# controller_rev3.net
KiCad netlist of a schematic drawn in EAGLE
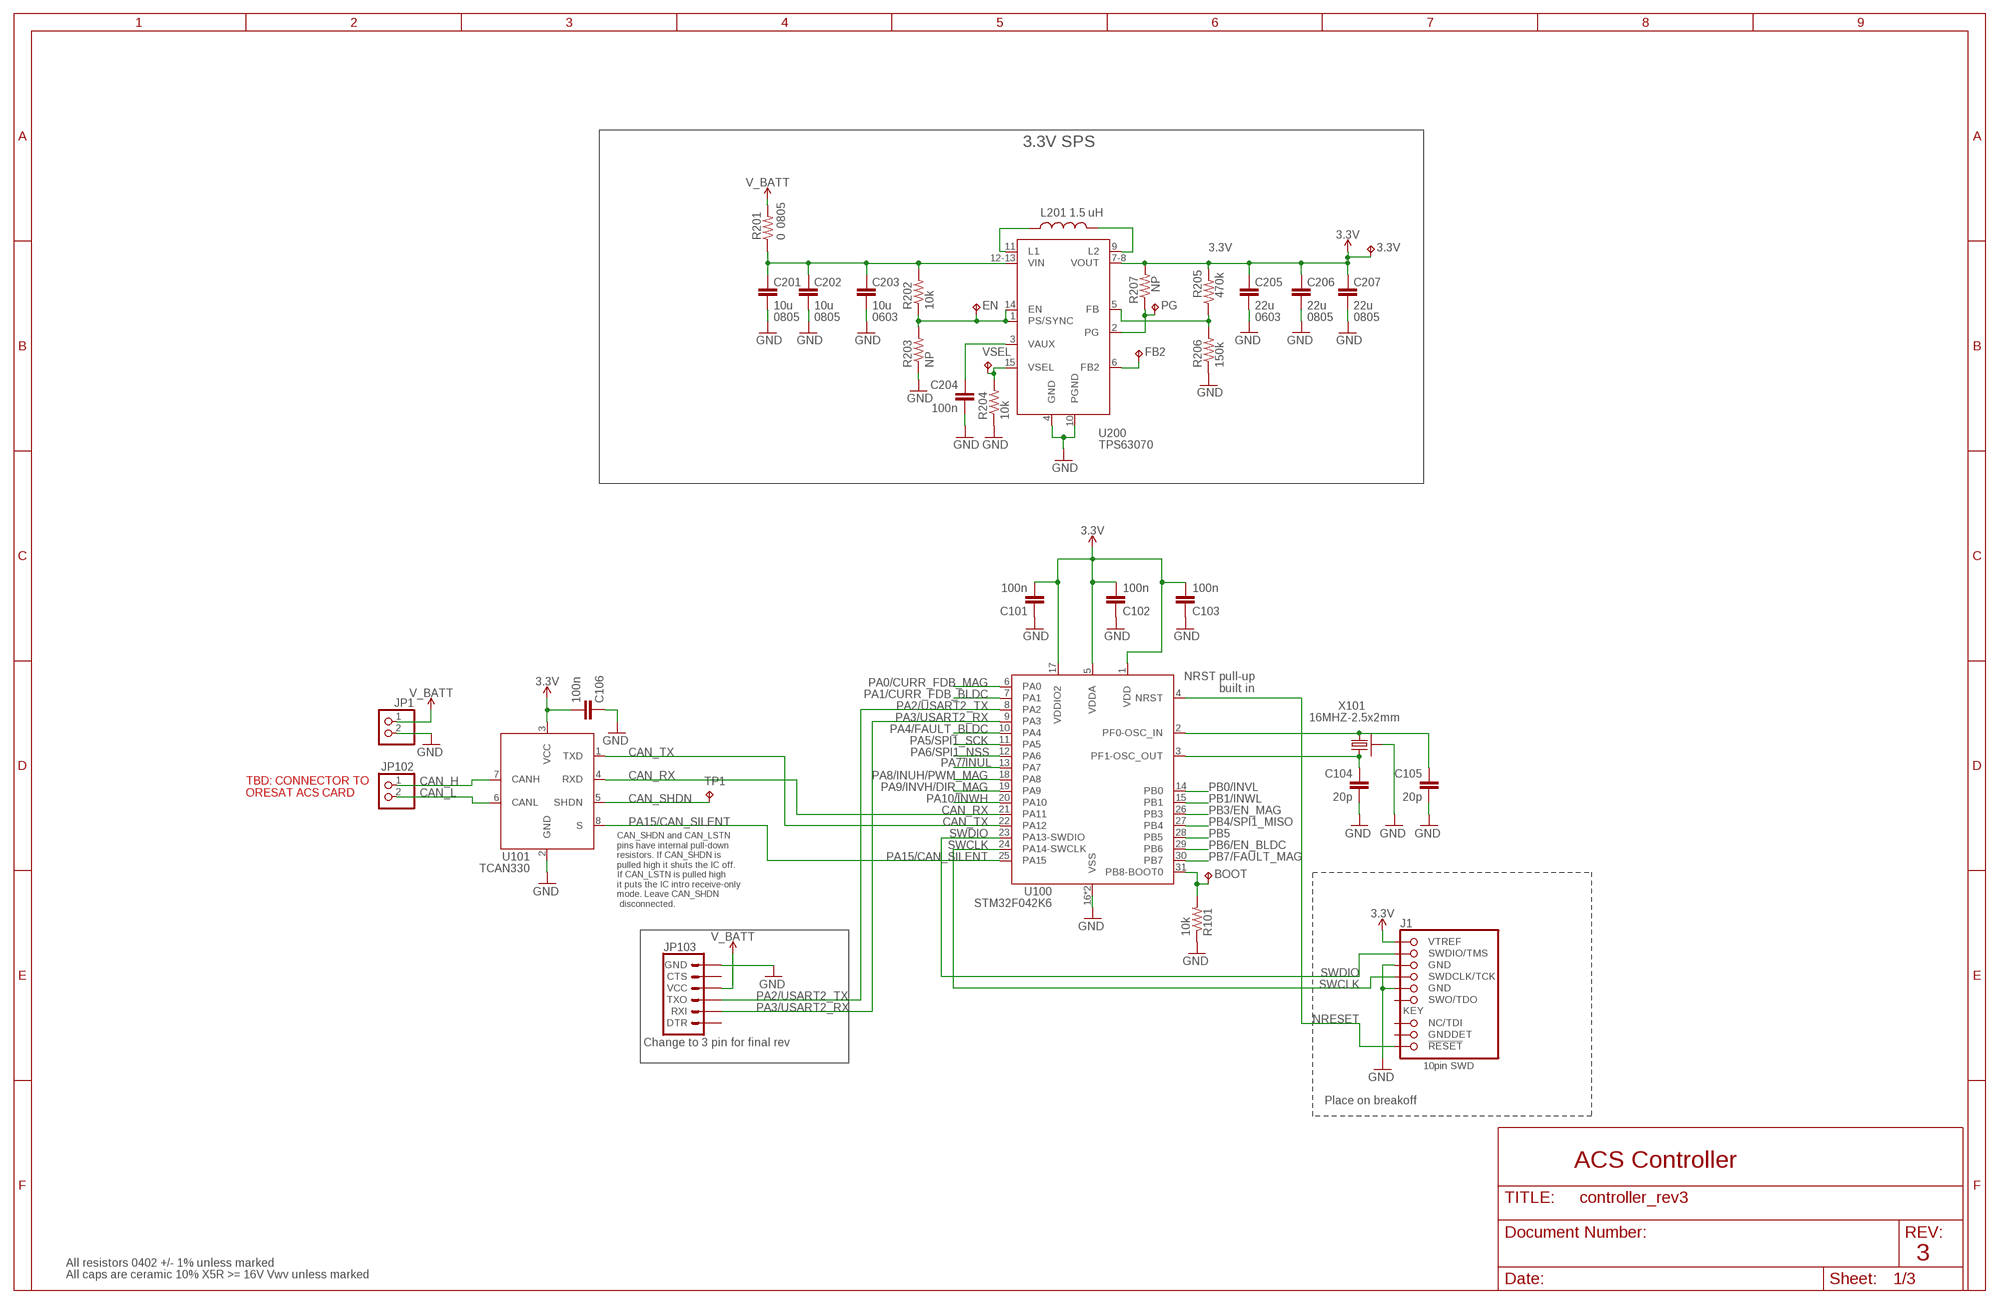
[diagram p0: schematic, sheet 1]
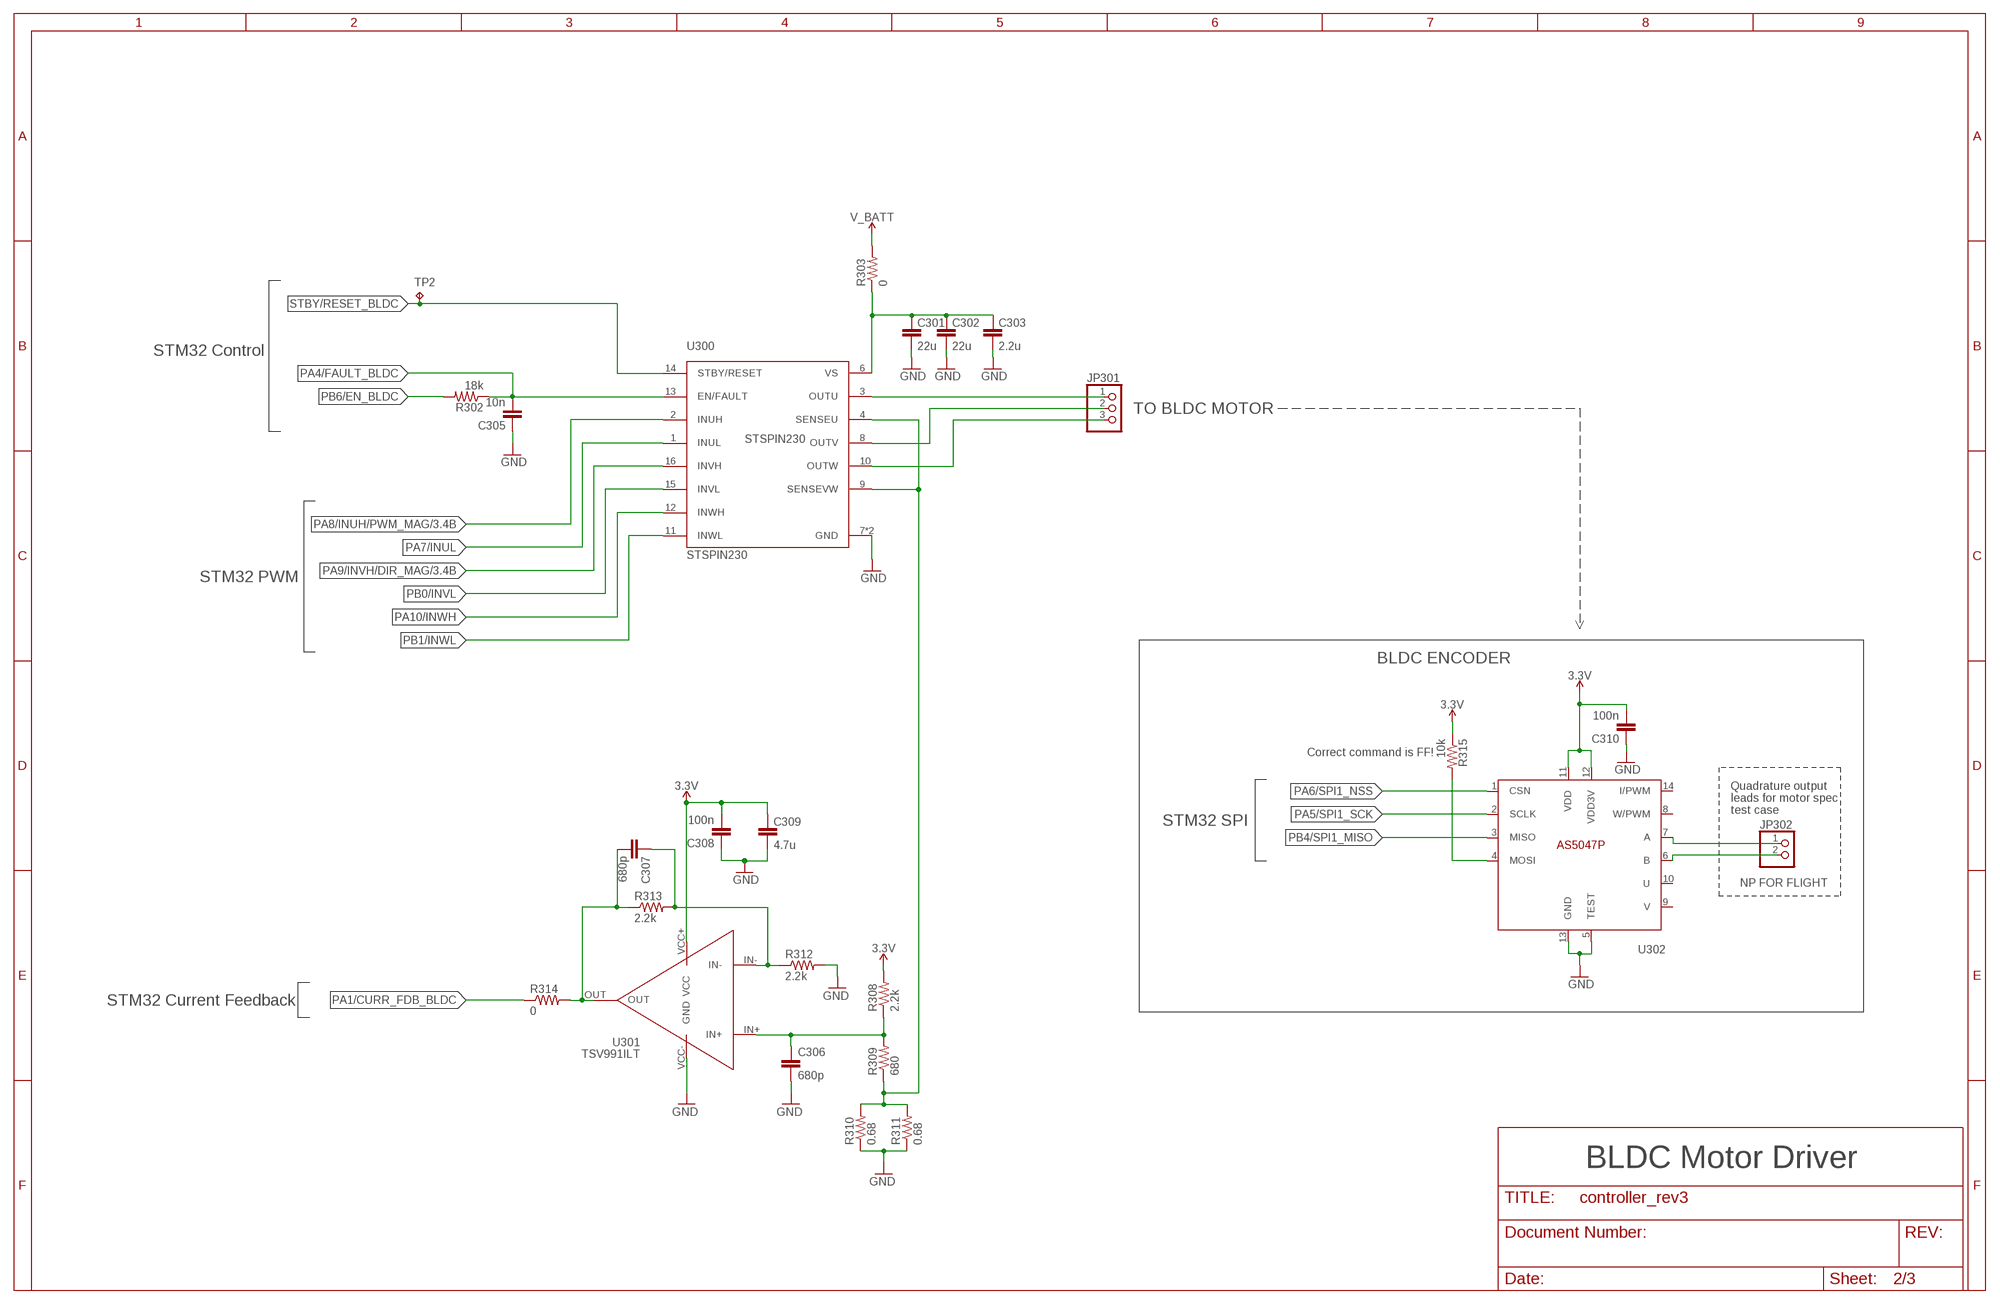
[diagram p1: schematic, sheet 2]
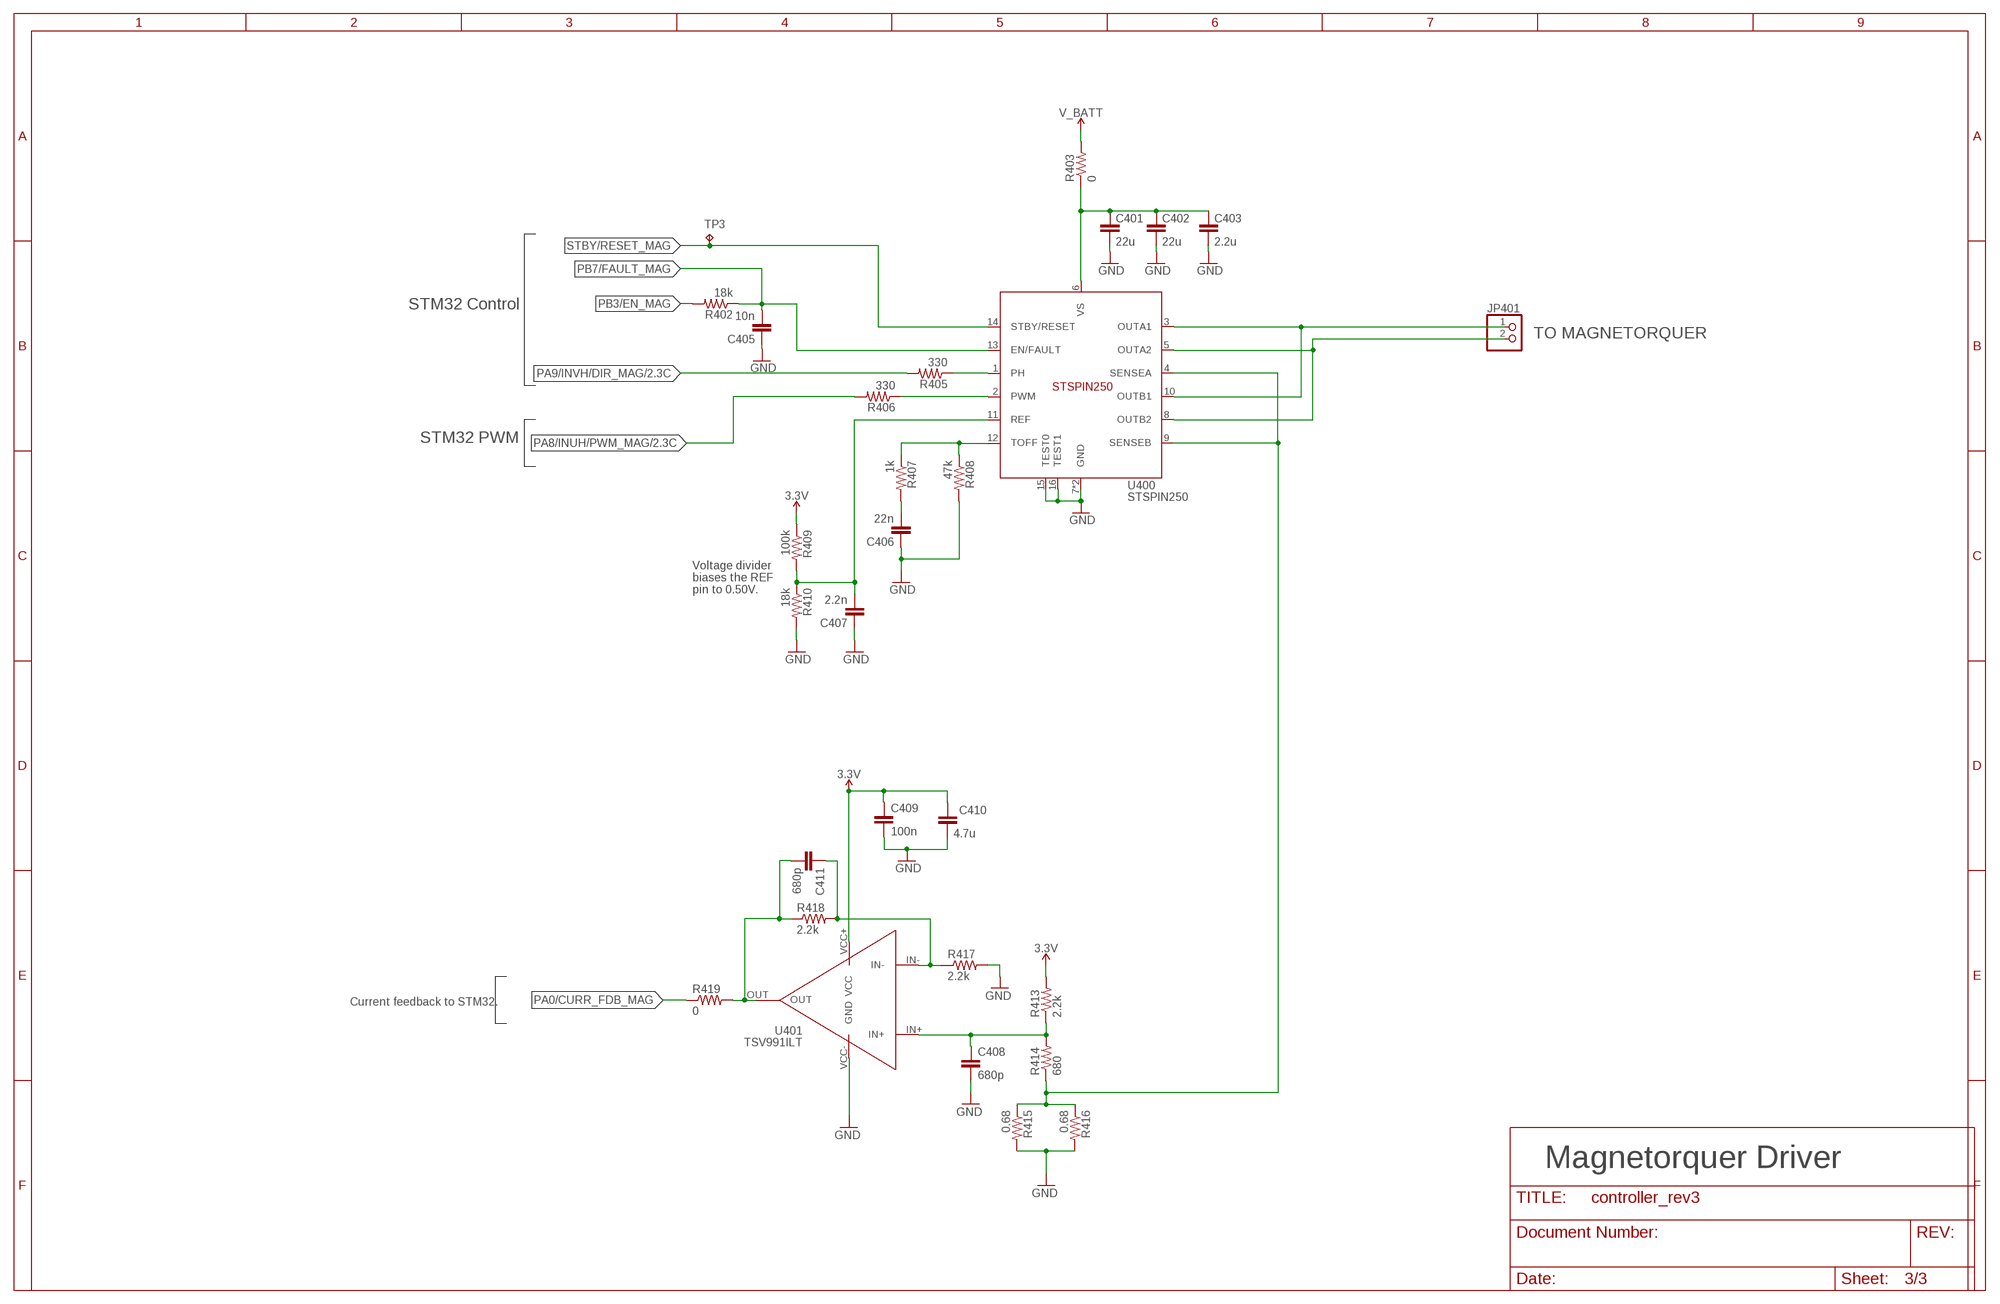
[diagram p2: schematic, sheet 3]

(export (version "E")
  (design (tool "Eeschema 10.0.6"))
  (components
    (comp (ref "C301")
      (value "22u")
      (footprint "eagle-import:.0603-B-NOSILK")
      (fields (field (name "MFR") "Samsung") (field (name "MPN") "CL05B104KO5NNNC"))
      (libsource (lib "eagle-import") (part "C-EU0603-B-NOSILK"))
    )
    (comp (ref "C302")
      (value "22u")
      (footprint "eagle-import:.0603-B-NOSILK")
      (fields (field (name "MFR") "Samsung") (field (name "MPN") "CL05B104KO5NNNC"))
      (libsource (lib "eagle-import") (part "C-EU0603-B-NOSILK"))
    )
    (comp (ref "C303")
      (value "2.2u")
      (footprint "eagle-import:.0603-B-NOSILK")
      (fields (field (name "MFR") "Samsung") (field (name "MPN") "CL05B104KO5NNNC"))
      (libsource (lib "eagle-import") (part "C-EU0603-B-NOSILK"))
    )
    (comp (ref "C305")
      (value "10n")
      (footprint "eagle-import:.0402-B-NOSILK")
      (fields (field (name "MFR") "Samsung") (field (name "MPN") "CL05B104KO5NNNC"))
      (libsource (lib "eagle-import") (part "rcl_custom_C-EU0402-B-NOSILK"))
    )
    (comp (ref "C306")
      (value "680p")
      (footprint "eagle-import:.0402-B-NOSILK")
      (fields (field (name "MFR") "Samsung") (field (name "MPN") "CL05B104KO5NNNC"))
      (libsource (lib "eagle-import") (part "rcl_custom_C-EU0402-B-NOSILK"))
    )
    (comp (ref "C307")
      (value "680p")
      (footprint "eagle-import:.0402-B-NOSILK")
      (fields (field (name "MFR") "Samsung") (field (name "MPN") "CL05B104KO5NNNC"))
      (libsource (lib "eagle-import") (part "rcl_custom_C-EU0402-B-NOSILK"))
    )
    (comp (ref "C308")
      (value "100n")
      (footprint "eagle-import:.0402-B-NOSILK")
      (fields (field (name "MFR") "Samsung") (field (name "MPN") "CL05B104KO5NNNC"))
      (libsource (lib "eagle-import") (part "rcl_custom_C-EU0402-B-NOSILK"))
    )
    (comp (ref "C309")
      (value "4.7u")
      (footprint "eagle-import:.0603-B-NOSILK")
      (fields (field (name "MFR") "Samsung") (field (name "MPN") "CL05B104KO5NNNC"))
      (libsource (lib "eagle-import") (part "C-EU0603-B-NOSILK"))
    )
    (comp (ref "C310")
      (value "100n")
      (footprint "eagle-import:.0402-B-NOSILK")
      (fields (field (name "MFR") "Samsung") (field (name "MPN") "CL05B104KO5NNNC"))
      (libsource (lib "eagle-import") (part "rcl_custom_C-EU0402-B-NOSILK"))
    )
    (comp (ref "JP301")
      (value "PINHD-1X03_2.00")
      (footprint "eagle-import:1X03M")
      (libsource (lib "eagle-import") (part "PINHD-1X03_2.00"))
    )
    (comp (ref "JP302")
      (value "PINHD-1X2")
      (footprint "eagle-import:1X02")
      (libsource (lib "eagle-import") (part "PINHD-1X2"))
    )
    (comp (ref "R302")
      (value "18k")
      (footprint "eagle-import:.0402-B-NOSILK")
      (fields (field (name "MFR") "Samsung") (field (name "MPN") "RC1005F6653CS"))
      (libsource (lib "eagle-import") (part "rcl_custom_R-US_0402-B-NOSILK"))
    )
    (comp (ref "R303")
      (value "0")
      (footprint "eagle-import:.0805-B-NOSILK")
      (libsource (lib "eagle-import") (part "R-US_0805-B-NOSILK"))
    )
    (comp (ref "R308")
      (value "2.2k")
      (footprint "eagle-import:.0402-B-NOSILK")
      (fields (field (name "MFR") "Samsung") (field (name "MPN") "RC1005F6653CS"))
      (libsource (lib "eagle-import") (part "rcl_custom_R-US_0402-B-NOSILK"))
    )
    (comp (ref "R309")
      (value "680")
      (footprint "eagle-import:.0402-B-NOSILK")
      (fields (field (name "MFR") "Samsung") (field (name "MPN") "RC1005F6653CS"))
      (libsource (lib "eagle-import") (part "rcl_custom_R-US_0402-B-NOSILK"))
    )
    (comp (ref "R310")
      (value "0.68")
      (footprint "eagle-import:.0805-B-NOSILK")
      (libsource (lib "eagle-import") (part "R-US_0805-B-NOSILK"))
    )
    (comp (ref "R311")
      (value "0.68")
      (footprint "eagle-import:.0805-B-NOSILK")
      (libsource (lib "eagle-import") (part "R-US_0805-B-NOSILK"))
    )
    (comp (ref "R312")
      (value "2.2k")
      (footprint "eagle-import:.0402-B-NOSILK")
      (fields (field (name "MFR") "Samsung") (field (name "MPN") "RC1005F6653CS"))
      (libsource (lib "eagle-import") (part "rcl_custom_R-US_0402-B-NOSILK"))
    )
    (comp (ref "R313")
      (value "2.2k")
      (footprint "eagle-import:.0402-B-NOSILK")
      (fields (field (name "MFR") "Samsung") (field (name "MPN") "RC1005F6653CS"))
      (libsource (lib "eagle-import") (part "rcl_custom_R-US_0402-B-NOSILK"))
    )
    (comp (ref "R314")
      (value "0")
      (footprint "eagle-import:.0402-B-NOSILK")
      (fields (field (name "MFR") "Samsung") (field (name "MPN") "RC1005F6653CS"))
      (libsource (lib "eagle-import") (part "rcl_custom_R-US_0402-B-NOSILK"))
    )
    (comp (ref "R315")
      (value "10k")
      (footprint "eagle-import:.0402-B-NOSILK")
      (fields (field (name "MFR") "Samsung") (field (name "MPN") "RC1005F6653CS"))
      (libsource (lib "eagle-import") (part "rcl_custom_R-US_0402-B-NOSILK"))
    )
    (comp (ref "TP2")
      (value "TPTP06R")
      (footprint "eagle-import:TP06R")
      (libsource (lib "eagle-import") (part "TPTP06R"))
    )
    (comp (ref "U300")
      (value "STSPIN230")
      (footprint "eagle-import:VFQFPN")
      (libsource (lib "eagle-import") (part "STSPIN230"))
    )
    (comp (ref "U301")
      (value "TSV991ILT")
      (footprint "eagle-import:SOT23-5")
      (libsource (lib "eagle-import") (part "TSV991ILT"))
    )
    (comp (ref "U302")
      (value "AS5047P")
      (footprint "eagle-import:TSSOP14")
      (libsource (lib "eagle-import") (part "AS5047P"))
    )
    (comp (ref "3.3V")
      (value "TPTP15SQ")
      (footprint "eagle-import:TP15SQ")
      (libsource (lib "eagle-import") (part "TPTP15SQ"))
    )
    (comp (ref "BOOT")
      (value "TPTP15SQ")
      (footprint "eagle-import:TP15SQ")
      (libsource (lib "eagle-import") (part "TPTP15SQ"))
    )
    (comp (ref "C101")
      (value "100n")
      (footprint "eagle-import:.0402-B-NOSILK")
      (fields (field (name "MFR") "Samsung") (field (name "MPN") "CL05B104KO5NNNC"))
      (libsource (lib "eagle-import") (part "rcl_custom_C-EU0402-B-NOSILK"))
    )
    (comp (ref "C102")
      (value "100n")
      (footprint "eagle-import:.0402-B-NOSILK")
      (fields (field (name "MFR") "Samsung") (field (name "MPN") "CL05B104KO5NNNC"))
      (libsource (lib "eagle-import") (part "rcl_custom_C-EU0402-B-NOSILK"))
    )
    (comp (ref "C103")
      (value "100n")
      (footprint "eagle-import:.0402-B-NOSILK")
      (fields (field (name "MFR") "Samsung") (field (name "MPN") "CL05B104KO5NNNC"))
      (libsource (lib "eagle-import") (part "rcl_custom_C-EU0402-B-NOSILK"))
    )
    (comp (ref "C104")
      (value "20p")
      (footprint "eagle-import:.0402-B-NOSILK")
      (fields (field (name "MFR") "Samsung") (field (name "MPN") "CL05C200JB51PNC"))
      (libsource (lib "eagle-import") (part "rcl_custom_C-EU0402-B-NOSILK"))
    )
    (comp (ref "C105")
      (value "20p")
      (footprint "eagle-import:.0402-B-NOSILK")
      (fields (field (name "MFR") "Samsung") (field (name "MPN") "CL05C200JB51PNC"))
      (libsource (lib "eagle-import") (part "rcl_custom_C-EU0402-B-NOSILK"))
    )
    (comp (ref "C106")
      (value "100n")
      (footprint "eagle-import:.0402-B-NOSILK")
      (fields (field (name "MFR") "Samsung") (field (name "MPN") "CL05B104KO5NNNC"))
      (libsource (lib "eagle-import") (part "rcl_custom_C-EU0402-B-NOSILK"))
    )
    (comp (ref "C201")
      (value "10u")
      (footprint "eagle-import:.0805-B-NOSILK")
      (libsource (lib "eagle-import") (part "C-EU0805-B-NOSILK"))
    )
    (comp (ref "C202")
      (value "10u")
      (footprint "eagle-import:.0805-B-NOSILK")
      (libsource (lib "eagle-import") (part "C-EU0805-B-NOSILK"))
    )
    (comp (ref "C203")
      (value "10u")
      (footprint "eagle-import:.0603-B-NOSILK")
      (fields (field (name "MFR") "Samsung") (field (name "MPN") "CL05B104KO5NNNC"))
      (libsource (lib "eagle-import") (part "C-EU0603-B-NOSILK"))
    )
    (comp (ref "C204")
      (value "100n")
      (footprint "eagle-import:.0402-B-NOSILK")
      (fields (field (name "MFR") "Samsung") (field (name "MPN") "CL05B104KO5NNNC"))
      (libsource (lib "eagle-import") (part "rcl_custom_C-EU0402-B-NOSILK"))
    )
    (comp (ref "C205")
      (value "22u")
      (footprint "eagle-import:.0603-B-NOSILK")
      (fields (field (name "MFR") "Samsung") (field (name "MPN") "CL05B104KO5NNNC"))
      (libsource (lib "eagle-import") (part "C-EU0603-B-NOSILK"))
    )
    (comp (ref "C206")
      (value "22u")
      (footprint "eagle-import:.0805-B-NOSILK")
      (libsource (lib "eagle-import") (part "C-EU0805-B-NOSILK"))
    )
    (comp (ref "C207")
      (value "22u")
      (footprint "eagle-import:.0805-B-NOSILK")
      (libsource (lib "eagle-import") (part "C-EU0805-B-NOSILK"))
    )
    (comp (ref "EN")
      (value "TPTP15SQ")
      (footprint "eagle-import:TP15SQ")
      (libsource (lib "eagle-import") (part "TPTP15SQ"))
    )
    (comp (ref "FB2")
      (value "TPTP15SQ")
      (footprint "eagle-import:TP15SQ")
      (libsource (lib "eagle-import") (part "TPTP15SQ"))
    )
    (comp (ref "J1")
      (value "1.27MM-SWD-CONNECTOR")
      (footprint "eagle-import:1.27MM_2X5")
      (libsource (lib "eagle-import") (part "1.27MM-SWD-CONNECTOR"))
    )
    (comp (ref "JP1")
      (value "PINHD-1X2")
      (footprint "eagle-import:1X02")
      (libsource (lib "eagle-import") (part "PINHD-1X2"))
    )
    (comp (ref "JP102")
      (value "PINHD-1X2")
      (footprint "eagle-import:1X02")
      (libsource (lib "eagle-import") (part "PINHD-1X2"))
    )
    (comp (ref "JP103")
      (value "6_PIN_SERIAL_TARGETSILK")
      (footprint "eagle-import:6_PIN_SERIAL_TARGET_SIDE_W_SILK")
      (libsource (lib "eagle-import") (part "6_PIN_SERIAL_TARGETSILK"))
    )
    (comp (ref "L201")
      (value "1.5 uH")
      (footprint "eagle-import:L-COILCRAFT-XFL4020")
      (fields (field (name "MFR") "Coilcraft") (field (name "MPN") "XFL4020-152ME"))
      (libsource (lib "eagle-import") (part "L-COILCRAFT-XFL4020"))
    )
    (comp (ref "PG")
      (value "TPTP15SQ")
      (footprint "eagle-import:TP15SQ")
      (libsource (lib "eagle-import") (part "TPTP15SQ"))
    )
    (comp (ref "R101")
      (value "10k")
      (footprint "eagle-import:.0402-B-NOSILK")
      (fields (field (name "MFR") "Samsung") (field (name "MPN") "RC1005F6653CS"))
      (libsource (lib "eagle-import") (part "rcl_custom_R-US_0402-B-NOSILK"))
    )
    (comp (ref "R201")
      (value "0")
      (footprint "eagle-import:.0805-B-NOSILK")
      (fields (field (name "MFR") "Rohm") (field (name "MPN") "MCR10EZPJ000"))
      (libsource (lib "eagle-import") (part "rcl_custom_R-US_0805-B-NOSILK"))
    )
    (comp (ref "R202")
      (value "10k")
      (footprint "eagle-import:.0402-B-NOSILK")
      (fields (field (name "MFR") "Samsung") (field (name "MPN") "RC1005F6653CS"))
      (libsource (lib "eagle-import") (part "rcl_custom_R-US_0402-B-NOSILK"))
    )
    (comp (ref "R203")
      (value "NP")
      (footprint "eagle-import:.0402-B-NOSILK")
      (fields (field (name "MFR") "Samsung") (field (name "MPN") "RC1005F6653CS"))
      (libsource (lib "eagle-import") (part "rcl_custom_R-US_0402-B-NOSILK"))
    )
    (comp (ref "R204")
      (value "10k")
      (footprint "eagle-import:.0402-B-NOSILK")
      (fields (field (name "MFR") "Samsung") (field (name "MPN") "RC1005F6653CS"))
      (libsource (lib "eagle-import") (part "rcl_custom_R-US_0402-B-NOSILK"))
    )
    (comp (ref "R205")
      (value "470k")
      (footprint "eagle-import:.0402-B-NOSILK")
      (fields (field (name "MFR") "Samsung") (field (name "MPN") "RC1005F6653CS"))
      (libsource (lib "eagle-import") (part "rcl_custom_R-US_0402-B-NOSILK"))
    )
    (comp (ref "R206")
      (value "150k")
      (footprint "eagle-import:.0402-B-NOSILK")
      (fields (field (name "MFR") "Samsung") (field (name "MPN") "RC1005F6653CS"))
      (libsource (lib "eagle-import") (part "rcl_custom_R-US_0402-B-NOSILK"))
    )
    (comp (ref "R207")
      (value "NP")
      (footprint "eagle-import:.0402-B-NOSILK")
      (fields (field (name "MFR") "Samsung") (field (name "MPN") "RC1005F6653CS"))
      (libsource (lib "eagle-import") (part "rcl_custom_R-US_0402-B-NOSILK"))
    )
    (comp (ref "TP1")
      (value "TPTP06R")
      (footprint "eagle-import:TP06R")
      (libsource (lib "eagle-import") (part "TPTP06R"))
    )
    (comp (ref "U100")
      (value "STM32F042K6")
      (footprint "eagle-import:QFP32-7X7")
      (fields (field (name "MFR") "STMicroelectronics") (field (name "MPN") "STM32F042K6T7"))
      (libsource (lib "eagle-import") (part "STM32F042K6"))
    )
    (comp (ref "U101")
      (value "TCAN330")
      (footprint "eagle-import:SOT23-8_TI-DCN")
      (fields (field (name "MFR") "Texas Instruments") (field (name "MPN") "TCAN330GDCNT"))
      (libsource (lib "eagle-import") (part "TCAN330"))
    )
    (comp (ref "U200")
      (value "TPS63070")
      (footprint "eagle-import:TPS63070X")
      (libsource (lib "eagle-import") (part "TPS63070X"))
    )
    (comp (ref "VSEL")
      (value "TPTP15SQ")
      (footprint "eagle-import:TP15SQ")
      (libsource (lib "eagle-import") (part "TPTP15SQ"))
    )
    (comp (ref "X101")
      (value "16MHZ-2.5x2mm")
      (footprint "eagle-import:CRYSTAL_2.5X2")
      (fields (field (name "MFR") "ECS Inc.") (field (name "MPN") "ECS-160-10-36Q-ES-TR"))
      (libsource (lib "eagle-import") (part "CRYSTAL-WITH-GND"))
    )
    (comp (ref "C401")
      (value "22u")
      (footprint "eagle-import:.0603-B-NOSILK")
      (fields (field (name "MFR") "Samsung") (field (name "MPN") "CL05B104KO5NNNC"))
      (libsource (lib "eagle-import") (part "C-EU0603-B-NOSILK"))
    )
    (comp (ref "C402")
      (value "22u")
      (footprint "eagle-import:.0603-B-NOSILK")
      (fields (field (name "MFR") "Samsung") (field (name "MPN") "CL05B104KO5NNNC"))
      (libsource (lib "eagle-import") (part "C-EU0603-B-NOSILK"))
    )
    (comp (ref "C403")
      (value "2.2u")
      (footprint "eagle-import:.0603-B-NOSILK")
      (fields (field (name "MFR") "Samsung") (field (name "MPN") "CL05B104KO5NNNC"))
      (libsource (lib "eagle-import") (part "C-EU0603-B-NOSILK"))
    )
    (comp (ref "C405")
      (value "10n")
      (footprint "eagle-import:.0402-B-NOSILK")
      (fields (field (name "MFR") "Samsung") (field (name "MPN") "CL05B104KO5NNNC"))
      (libsource (lib "eagle-import") (part "rcl_custom_C-EU0402-B-NOSILK"))
    )
    (comp (ref "C406")
      (value "22n")
      (footprint "eagle-import:.0402-B-NOSILK")
      (fields (field (name "MFR") "Samsung") (field (name "MPN") "CL05B104KO5NNNC"))
      (libsource (lib "eagle-import") (part "rcl_custom_C-EU0402-B-NOSILK"))
    )
    (comp (ref "C407")
      (value "2.2n")
      (footprint "eagle-import:.0402-B-NOSILK")
      (fields (field (name "MFR") "Samsung") (field (name "MPN") "CL05B104KO5NNNC"))
      (libsource (lib "eagle-import") (part "rcl_custom_C-EU0402-B-NOSILK"))
    )
    (comp (ref "C408")
      (value "680p")
      (footprint "eagle-import:.0402-B-NOSILK")
      (fields (field (name "MFR") "Samsung") (field (name "MPN") "CL05B104KO5NNNC"))
      (libsource (lib "eagle-import") (part "rcl_custom_C-EU0402-B-NOSILK"))
    )
    (comp (ref "C409")
      (value "100n")
      (footprint "eagle-import:.0402-B-NOSILK")
      (fields (field (name "MFR") "Samsung") (field (name "MPN") "CL05B104KO5NNNC"))
      (libsource (lib "eagle-import") (part "rcl_custom_C-EU0402-B-NOSILK"))
    )
    (comp (ref "C410")
      (value "4.7u")
      (footprint "eagle-import:.0603-B-NOSILK")
      (fields (field (name "MFR") "Samsung") (field (name "MPN") "CL05B104KO5NNNC"))
      (libsource (lib "eagle-import") (part "C-EU0603-B-NOSILK"))
    )
    (comp (ref "C411")
      (value "680p")
      (footprint "eagle-import:.0402-B-NOSILK")
      (fields (field (name "MFR") "Samsung") (field (name "MPN") "CL05B104KO5NNNC"))
      (libsource (lib "eagle-import") (part "rcl_custom_C-EU0402-B-NOSILK"))
    )
    (comp (ref "JP401")
      (value "PINHD-1X2")
      (footprint "eagle-import:1X02")
      (libsource (lib "eagle-import") (part "PINHD-1X2"))
    )
    (comp (ref "R402")
      (value "18k")
      (footprint "eagle-import:.0402-B-NOSILK")
      (fields (field (name "MFR") "Samsung") (field (name "MPN") "RC1005F6653CS"))
      (libsource (lib "eagle-import") (part "rcl_custom_R-US_0402-B-NOSILK"))
    )
    (comp (ref "R403")
      (value "0")
      (footprint "eagle-import:.0805-B-NOSILK")
      (libsource (lib "eagle-import") (part "R-US_0805-B-NOSILK"))
    )
    (comp (ref "R405")
      (value "330")
      (footprint "eagle-import:.0402-B-NOSILK")
      (fields (field (name "MFR") "Samsung") (field (name "MPN") "RC1005F6653CS"))
      (libsource (lib "eagle-import") (part "rcl_custom_R-US_0402-B-NOSILK"))
    )
    (comp (ref "R406")
      (value "330")
      (footprint "eagle-import:.0402-B-NOSILK")
      (fields (field (name "MFR") "Samsung") (field (name "MPN") "RC1005F6653CS"))
      (libsource (lib "eagle-import") (part "rcl_custom_R-US_0402-B-NOSILK"))
    )
    (comp (ref "R407")
      (value "1k")
      (footprint "eagle-import:.0402-B-NOSILK")
      (fields (field (name "MFR") "Samsung") (field (name "MPN") "RC1005F6653CS"))
      (libsource (lib "eagle-import") (part "rcl_custom_R-US_0402-B-NOSILK"))
    )
    (comp (ref "R408")
      (value "47k")
      (footprint "eagle-import:.0402-B-NOSILK")
      (fields (field (name "MFR") "Samsung") (field (name "MPN") "RC1005F6653CS"))
      (libsource (lib "eagle-import") (part "rcl_custom_R-US_0402-B-NOSILK"))
    )
    (comp (ref "R409")
      (value "100k")
      (footprint "eagle-import:.0402-B-NOSILK")
      (fields (field (name "MFR") "Samsung") (field (name "MPN") "RC1005F6653CS"))
      (libsource (lib "eagle-import") (part "rcl_custom_R-US_0402-B-NOSILK"))
    )
    (comp (ref "R410")
      (value "18k")
      (footprint "eagle-import:.0402-B-NOSILK")
      (fields (field (name "MFR") "Samsung") (field (name "MPN") "RC1005F6653CS"))
      (libsource (lib "eagle-import") (part "rcl_custom_R-US_0402-B-NOSILK"))
    )
    (comp (ref "R413")
      (value "2.2k")
      (footprint "eagle-import:.0402-B-NOSILK")
      (fields (field (name "MFR") "Samsung") (field (name "MPN") "RC1005F6653CS"))
      (libsource (lib "eagle-import") (part "rcl_custom_R-US_0402-B-NOSILK"))
    )
    (comp (ref "R414")
      (value "680")
      (footprint "eagle-import:.0402-B-NOSILK")
      (fields (field (name "MFR") "Samsung") (field (name "MPN") "RC1005F6653CS"))
      (libsource (lib "eagle-import") (part "rcl_custom_R-US_0402-B-NOSILK"))
    )
    (comp (ref "R415")
      (value "0.68")
      (footprint "eagle-import:.0805-B-NOSILK")
      (libsource (lib "eagle-import") (part "R-US_0805-B-NOSILK"))
    )
    (comp (ref "R416")
      (value "0.68")
      (footprint "eagle-import:.0805-B-NOSILK")
      (libsource (lib "eagle-import") (part "R-US_0805-B-NOSILK"))
    )
    (comp (ref "R417")
      (value "2.2k")
      (footprint "eagle-import:.0402-B-NOSILK")
      (fields (field (name "MFR") "Samsung") (field (name "MPN") "RC1005F6653CS"))
      (libsource (lib "eagle-import") (part "rcl_custom_R-US_0402-B-NOSILK"))
    )
    (comp (ref "R418")
      (value "2.2k")
      (footprint "eagle-import:.0402-B-NOSILK")
      (fields (field (name "MFR") "Samsung") (field (name "MPN") "RC1005F6653CS"))
      (libsource (lib "eagle-import") (part "rcl_custom_R-US_0402-B-NOSILK"))
    )
    (comp (ref "R419")
      (value "0")
      (footprint "eagle-import:.0402-B-NOSILK")
      (fields (field (name "MFR") "Samsung") (field (name "MPN") "RC1005F6653CS"))
      (libsource (lib "eagle-import") (part "rcl_custom_R-US_0402-B-NOSILK"))
    )
    (comp (ref "TP3")
      (value "TPTP06R")
      (footprint "eagle-import:TP06R")
      (libsource (lib "eagle-import") (part "TPTP06R"))
    )
    (comp (ref "U400")
      (value "STSPIN250")
      (footprint "eagle-import:VFQPN")
      (libsource (lib "eagle-import") (part "STSPIN250"))
    )
    (comp (ref "U401")
      (value "TSV991ILT")
      (footprint "eagle-import:SOT23-5")
      (libsource (lib "eagle-import") (part "TSV991ILT"))
    )
  )
  (nets
    (net (code "1") (name "3.3V") (class "Default")
      (node (ref "3.3V") (pin "TP") (pinfunction "TP_TP") (pintype "input"))
      (node (ref "C101") (pin "2") (pinfunction "2_2") (pintype "passive"))
      (node (ref "C102") (pin "2") (pinfunction "2_2") (pintype "passive"))
      (node (ref "C103") (pin "2") (pinfunction "2_2") (pintype "passive"))
      (node (ref "C106") (pin "2") (pinfunction "2_2") (pintype "passive"))
      (node (ref "C205") (pin "1") (pinfunction "1_1") (pintype "passive"))
      (node (ref "C206") (pin "1") (pinfunction "1_1") (pintype "passive"))
      (node (ref "C207") (pin "1") (pinfunction "1_1") (pintype "passive"))
      (node (ref "C308") (pin "2") (pinfunction "2_2") (pintype "passive"))
      (node (ref "C309") (pin "1") (pinfunction "1_1") (pintype "passive"))
      (node (ref "C310") (pin "2") (pinfunction "2_2") (pintype "passive"))
      (node (ref "C409") (pin "1") (pinfunction "1_1") (pintype "passive"))
      (node (ref "C410") (pin "1") (pinfunction "1_1") (pintype "passive"))
      (node (ref "J1") (pin "VTREF") (pinfunction "VTREF_VTREF") (pintype "passive"))
      (node (ref "R205") (pin "2") (pinfunction "2_2") (pintype "passive"))
      (node (ref "R207") (pin "2") (pinfunction "2_2") (pintype "passive"))
      (node (ref "R308") (pin "2") (pinfunction "2_2") (pintype "passive"))
      (node (ref "R315") (pin "1") (pinfunction "1_1") (pintype "passive"))
      (node (ref "R409") (pin "1") (pinfunction "1_1") (pintype "passive"))
      (node (ref "R413") (pin "2") (pinfunction "2_2") (pintype "passive"))
      (node (ref "U100") (pin "1") (pinfunction "VDD_1") (pintype "power_in"))
      (node (ref "U100") (pin "17") (pinfunction "VDDIO2_17") (pintype "power_in"))
      (node (ref "U100") (pin "5") (pinfunction "VDDA_5") (pintype "power_in"))
      (node (ref "U101") (pin "3") (pinfunction "VCC_3") (pintype "power_in"))
      (node (ref "U200") (pin "7-8") (pinfunction "VOUT_7-8") (pintype "power_in"))
      (node (ref "U301") (pin "VCC+") (pinfunction "VCC_VCC+") (pintype "bidirectional"))
      (node (ref "U302") (pin "11") (pinfunction "VDD_11") (pintype "power_in"))
      (node (ref "U302") (pin "12") (pinfunction "VDD3V_12") (pintype "power_in"))
      (node (ref "U401") (pin "VCC+") (pinfunction "VCC_VCC+") (pintype "bidirectional"))
    )
    (net (code "2") (name "CAN_H") (class "Default")
      (node (ref "JP102") (pin "1") (pinfunction "1_1") (pintype "passive"))
      (node (ref "U101") (pin "7") (pinfunction "CANH_7") (pintype "bidirectional"))
    )
    (net (code "3") (name "CAN_L") (class "Default")
      (node (ref "JP102") (pin "2") (pinfunction "2_2") (pintype "passive"))
      (node (ref "U101") (pin "6") (pinfunction "CANL_6") (pintype "bidirectional"))
    )
    (net (code "4") (name "CAN_RX") (class "Default")
      (node (ref "U100") (pin "21") (pinfunction "PA11_21") (pintype "bidirectional"))
      (node (ref "U101") (pin "4") (pinfunction "RXD_4") (pintype "output"))
    )
    (net (code "5") (name "CAN_SHDN") (class "Default")
      (node (ref "TP1") (pin "TP") (pinfunction "TP_TP") (pintype "input"))
      (node (ref "U101") (pin "5") (pinfunction "SHDN_5") (pintype "input"))
    )
    (net (code "6") (name "CAN_TX") (class "Default")
      (node (ref "U100") (pin "22") (pinfunction "PA12_22") (pintype "bidirectional"))
      (node (ref "U101") (pin "1") (pinfunction "TXD_1") (pintype "input"))
    )
    (net (code "7") (name "GND") (class "Default")
      (node (ref "C101") (pin "1") (pinfunction "1_1") (pintype "passive"))
      (node (ref "C102") (pin "1") (pinfunction "1_1") (pintype "passive"))
      (node (ref "C103") (pin "1") (pinfunction "1_1") (pintype "passive"))
      (node (ref "C104") (pin "2") (pinfunction "2_2") (pintype "passive"))
      (node (ref "C105") (pin "2") (pinfunction "2_2") (pintype "passive"))
      (node (ref "C106") (pin "1") (pinfunction "1_1") (pintype "passive"))
      (node (ref "C201") (pin "2") (pinfunction "2_2") (pintype "passive"))
      (node (ref "C202") (pin "2") (pinfunction "2_2") (pintype "passive"))
      (node (ref "C203") (pin "2") (pinfunction "2_2") (pintype "passive"))
      (node (ref "C204") (pin "2") (pinfunction "2_2") (pintype "passive"))
      (node (ref "C205") (pin "2") (pinfunction "2_2") (pintype "passive"))
      (node (ref "C206") (pin "2") (pinfunction "2_2") (pintype "passive"))
      (node (ref "C207") (pin "2") (pinfunction "2_2") (pintype "passive"))
      (node (ref "C301") (pin "2") (pinfunction "2_2") (pintype "passive"))
      (node (ref "C302") (pin "2") (pinfunction "2_2") (pintype "passive"))
      (node (ref "C303") (pin "2") (pinfunction "2_2") (pintype "passive"))
      (node (ref "C305") (pin "1") (pinfunction "1_1") (pintype "passive"))
      (node (ref "C306") (pin "2") (pinfunction "2_2") (pintype "passive"))
      (node (ref "C308") (pin "1") (pinfunction "1_1") (pintype "passive"))
      (node (ref "C309") (pin "2") (pinfunction "2_2") (pintype "passive"))
      (node (ref "C310") (pin "1") (pinfunction "1_1") (pintype "passive"))
      (node (ref "C401") (pin "2") (pinfunction "2_2") (pintype "passive"))
      (node (ref "C402") (pin "2") (pinfunction "2_2") (pintype "passive"))
      (node (ref "C403") (pin "2") (pinfunction "2_2") (pintype "passive"))
      (node (ref "C405") (pin "1") (pinfunction "1_1") (pintype "passive"))
      (node (ref "C406") (pin "1") (pinfunction "1_1") (pintype "passive"))
      (node (ref "C407") (pin "1") (pinfunction "1_1") (pintype "passive"))
      (node (ref "C408") (pin "2") (pinfunction "2_2") (pintype "passive"))
      (node (ref "C409") (pin "2") (pinfunction "2_2") (pintype "passive"))
      (node (ref "C410") (pin "2") (pinfunction "2_2") (pintype "passive"))
      (node (ref "J1") (pin "GND") (pinfunction "GND_GND") (pintype "passive"))
      (node (ref "J1") (pin "GND@2") (pinfunction "GND_GND@2") (pintype "passive"))
      (node (ref "JP1") (pin "2") (pinfunction "2_2") (pintype "passive"))
      (node (ref "JP103") (pin "P$6") (pinfunction "GND_P$6") (pintype "passive"))
      (node (ref "R101") (pin "1") (pinfunction "1_1") (pintype "passive"))
      (node (ref "R203") (pin "1") (pinfunction "1_1") (pintype "passive"))
      (node (ref "R204") (pin "1") (pinfunction "1_1") (pintype "passive"))
      (node (ref "R206") (pin "1") (pinfunction "1_1") (pintype "passive"))
      (node (ref "R310") (pin "1") (pinfunction "1_1") (pintype "passive"))
      (node (ref "R311") (pin "1") (pinfunction "1_1") (pintype "passive"))
      (node (ref "R312") (pin "2") (pinfunction "2_2") (pintype "passive"))
      (node (ref "R408") (pin "2") (pinfunction "2_2") (pintype "passive"))
      (node (ref "R410") (pin "2") (pinfunction "2_2") (pintype "passive"))
      (node (ref "R415") (pin "2") (pinfunction "2_2") (pintype "passive"))
      (node (ref "R416") (pin "2") (pinfunction "2_2") (pintype "passive"))
      (node (ref "R417") (pin "2") (pinfunction "2_2") (pintype "passive"))
      (node (ref "U100") (pin "16") (pinfunction "VSS_16") (pintype "power_in"))
      (node (ref "U100") (pin "32") (pinfunction "VSS_32") (pintype "power_in"))
      (node (ref "U101") (pin "2") (pinfunction "GND_2") (pintype "power_in"))
      (node (ref "U200") (pin "10") (pinfunction "PGND_10") (pintype "power_in"))
      (node (ref "U200") (pin "4") (pinfunction "GND_4") (pintype "power_in"))
      (node (ref "U300") (pin "7") (pinfunction "GND_7") (pintype "power_in"))
      (node (ref "U300") (pin "EPAD") (pinfunction "GND_EPAD") (pintype "power_in"))
      (node (ref "U301") (pin "VCC-") (pinfunction "GND_VCC-") (pintype "bidirectional"))
      (node (ref "U302") (pin "13") (pinfunction "GND_13") (pintype "power_in"))
      (node (ref "U302") (pin "5") (pinfunction "TEST_5") (pintype "power_in"))
      (node (ref "U400") (pin "15") (pinfunction "TEST0_15") (pintype "bidirectional"))
      (node (ref "U400") (pin "16") (pinfunction "TEST1_16") (pintype "bidirectional"))
      (node (ref "U400") (pin "7") (pinfunction "GND_7") (pintype "power_in"))
      (node (ref "U400") (pin "EPAD") (pinfunction "GND_EPAD") (pintype "power_in"))
      (node (ref "U401") (pin "VCC-") (pinfunction "GND_VCC-") (pintype "bidirectional"))
      (node (ref "X101") (pin "2") (pinfunction "SHIELD_2") (pintype "power_in"))
      (node (ref "X101") (pin "4") (pinfunction "SHIELD_4") (pintype "power_in"))
    )
    (net (code "8") (name "NRESET") (class "Default")
      (node (ref "J1") (pin "!RESET") (pinfunction "~{RESET}_!RESET") (pintype "passive"))
      (node (ref "U100") (pin "4") (pinfunction "NRST_4") (pintype "bidirectional"))
    )
    (net (code "9") (name "Net-(C306-Pad1)") (class "Default")
      (node (ref "C306") (pin "1") (pinfunction "1_1") (pintype "passive"))
      (node (ref "R308") (pin "1") (pinfunction "1_1") (pintype "passive"))
      (node (ref "R309") (pin "2") (pinfunction "2_2") (pintype "passive"))
      (node (ref "U301") (pin "IN+") (pinfunction "IN+_IN+") (pintype "bidirectional"))
    )
    (net (code "10") (name "Net-(C307-Pad1)") (class "Default")
      (node (ref "C307") (pin "1") (pinfunction "1_1") (pintype "passive"))
      (node (ref "R312") (pin "1") (pinfunction "1_1") (pintype "passive"))
      (node (ref "R313") (pin "2") (pinfunction "2_2") (pintype "passive"))
      (node (ref "U301") (pin "IN-") (pinfunction "IN-_IN-") (pintype "bidirectional"))
    )
    (net (code "11") (name "Net-(C307-Pad2)") (class "Default")
      (node (ref "C307") (pin "2") (pinfunction "2_2") (pintype "passive"))
      (node (ref "R313") (pin "1") (pinfunction "1_1") (pintype "passive"))
      (node (ref "R314") (pin "2") (pinfunction "2_2") (pintype "passive"))
      (node (ref "U301") (pin "OUT") (pinfunction "OUT_OUT") (pintype "bidirectional"))
    )
    (net (code "12") (name "Net-(C406-Pad2)") (class "Default")
      (node (ref "C406") (pin "2") (pinfunction "2_2") (pintype "passive"))
      (node (ref "R407") (pin "2") (pinfunction "2_2") (pintype "passive"))
    )
    (net (code "13") (name "Net-(C408-Pad1)") (class "Default")
      (node (ref "C408") (pin "1") (pinfunction "1_1") (pintype "passive"))
      (node (ref "R413") (pin "1") (pinfunction "1_1") (pintype "passive"))
      (node (ref "R414") (pin "2") (pinfunction "2_2") (pintype "passive"))
      (node (ref "U401") (pin "IN+") (pinfunction "IN+_IN+") (pintype "bidirectional"))
    )
    (net (code "14") (name "Net-(C411-Pad1)") (class "Default")
      (node (ref "C411") (pin "1") (pinfunction "1_1") (pintype "passive"))
      (node (ref "R417") (pin "1") (pinfunction "1_1") (pintype "passive"))
      (node (ref "R418") (pin "2") (pinfunction "2_2") (pintype "passive"))
      (node (ref "U401") (pin "IN-") (pinfunction "IN-_IN-") (pintype "bidirectional"))
    )
    (net (code "15") (name "Net-(C411-Pad2)") (class "Default")
      (node (ref "C411") (pin "2") (pinfunction "2_2") (pintype "passive"))
      (node (ref "R418") (pin "1") (pinfunction "1_1") (pintype "passive"))
      (node (ref "R419") (pin "2") (pinfunction "2_2") (pintype "passive"))
      (node (ref "U401") (pin "OUT") (pinfunction "OUT_OUT") (pintype "bidirectional"))
    )
    (net (code "16") (name "Net-(U100-PB8-BOOT0)") (class "Default")
      (node (ref "BOOT") (pin "TP") (pinfunction "TP_TP") (pintype "input"))
      (node (ref "R101") (pin "2") (pinfunction "2_2") (pintype "passive"))
      (node (ref "U100") (pin "31") (pinfunction "PB8-BOOT0_31") (pintype "bidirectional"))
    )
    (net (code "17") (name "Net-(U100-PF0-OSC_IN)") (class "Default")
      (node (ref "C105") (pin "1") (pinfunction "1_1") (pintype "passive"))
      (node (ref "U100") (pin "2") (pinfunction "PF0-OSC_IN_2") (pintype "bidirectional"))
      (node (ref "X101") (pin "1") (pinfunction "1_1") (pintype "passive"))
    )
    (net (code "18") (name "Net-(U100-PF1-OSC_OUT)") (class "Default")
      (node (ref "C104") (pin "1") (pinfunction "1_1") (pintype "passive"))
      (node (ref "U100") (pin "3") (pinfunction "PF1-OSC_OUT_3") (pintype "bidirectional"))
      (node (ref "X101") (pin "3") (pinfunction "2_3") (pintype "passive"))
    )
    (net (code "19") (name "Net-(U200-EN)") (class "Default")
      (node (ref "EN") (pin "TP") (pinfunction "TP_TP") (pintype "input"))
      (node (ref "R202") (pin "1") (pinfunction "1_1") (pintype "passive"))
      (node (ref "R203") (pin "2") (pinfunction "2_2") (pintype "passive"))
      (node (ref "U200") (pin "1") (pinfunction "PS/SYNC_1") (pintype "input"))
      (node (ref "U200") (pin "14") (pinfunction "EN_14") (pintype "input"))
    )
    (net (code "20") (name "Net-(U200-FB)") (class "Default")
      (node (ref "R205") (pin "1") (pinfunction "1_1") (pintype "passive"))
      (node (ref "R206") (pin "2") (pinfunction "2_2") (pintype "passive"))
      (node (ref "U200") (pin "5") (pinfunction "FB_5") (pintype "passive"))
    )
    (net (code "21") (name "Net-(U200-FB2)") (class "Default")
      (node (ref "FB2") (pin "TP") (pinfunction "TP_TP") (pintype "input"))
      (node (ref "U200") (pin "6") (pinfunction "FB2_6") (pintype "passive"))
    )
    (net (code "22") (name "Net-(U200-L1)") (class "Default")
      (node (ref "L201") (pin "1") (pinfunction "1_1") (pintype "passive"))
      (node (ref "U200") (pin "11") (pinfunction "L1_11") (pintype "passive"))
    )
    (net (code "23") (name "Net-(U200-L2)") (class "Default")
      (node (ref "L201") (pin "2") (pinfunction "2_2") (pintype "passive"))
      (node (ref "U200") (pin "9") (pinfunction "L2_9") (pintype "passive"))
    )
    (net (code "24") (name "Net-(U200-PG)") (class "Default")
      (node (ref "PG") (pin "TP") (pinfunction "TP_TP") (pintype "input"))
      (node (ref "R207") (pin "1") (pinfunction "1_1") (pintype "passive"))
      (node (ref "U200") (pin "2") (pinfunction "PG_2") (pintype "open_collector"))
    )
    (net (code "25") (name "Net-(U200-VAUX)") (class "Default")
      (node (ref "C204") (pin "1") (pinfunction "1_1") (pintype "passive"))
      (node (ref "U200") (pin "3") (pinfunction "VAUX_3") (pintype "output"))
    )
    (net (code "26") (name "Net-(U200-VIN)") (class "Default")
      (node (ref "C201") (pin "1") (pinfunction "1_1") (pintype "passive"))
      (node (ref "C202") (pin "1") (pinfunction "1_1") (pintype "passive"))
      (node (ref "C203") (pin "1") (pinfunction "1_1") (pintype "passive"))
      (node (ref "R201") (pin "1") (pinfunction "1_1") (pintype "passive"))
      (node (ref "R202") (pin "2") (pinfunction "2_2") (pintype "passive"))
      (node (ref "U200") (pin "12-13") (pinfunction "VIN_12-13") (pintype "power_in"))
    )
    (net (code "27") (name "Net-(U200-VSEL)") (class "Default")
      (node (ref "R204") (pin "2") (pinfunction "2_2") (pintype "passive"))
      (node (ref "U200") (pin "15") (pinfunction "VSEL_15") (pintype "input"))
      (node (ref "VSEL") (pin "TP") (pinfunction "TP_TP") (pintype "input"))
    )
    (net (code "28") (name "Net-(U300-OUTU)") (class "Default")
      (node (ref "JP301") (pin "1") (pinfunction "1_1") (pintype "passive"))
      (node (ref "U300") (pin "3") (pinfunction "OUTU_3") (pintype "output"))
    )
    (net (code "29") (name "Net-(U300-OUTV)") (class "Default")
      (node (ref "JP301") (pin "2") (pinfunction "2_2") (pintype "passive"))
      (node (ref "U300") (pin "8") (pinfunction "OUTV_8") (pintype "output"))
    )
    (net (code "30") (name "Net-(U300-OUTW)") (class "Default")
      (node (ref "JP301") (pin "3") (pinfunction "3_3") (pintype "passive"))
      (node (ref "U300") (pin "10") (pinfunction "OUTW_10") (pintype "output"))
    )
    (net (code "31") (name "Net-(U300-SENSEU)") (class "Default")
      (node (ref "R309") (pin "1") (pinfunction "1_1") (pintype "passive"))
      (node (ref "R310") (pin "2") (pinfunction "2_2") (pintype "passive"))
      (node (ref "R311") (pin "2") (pinfunction "2_2") (pintype "passive"))
      (node (ref "U300") (pin "4") (pinfunction "SENSEU_4") (pintype "output"))
      (node (ref "U300") (pin "9") (pinfunction "SENSEVW_9") (pintype "output"))
    )
    (net (code "32") (name "Net-(U300-VS)") (class "Default")
      (node (ref "C301") (pin "1") (pinfunction "1_1") (pintype "passive"))
      (node (ref "C302") (pin "1") (pinfunction "1_1") (pintype "passive"))
      (node (ref "C303") (pin "1") (pinfunction "1_1") (pintype "passive"))
      (node (ref "R303") (pin "1") (pinfunction "1_1") (pintype "passive"))
      (node (ref "U300") (pin "6") (pinfunction "VS_6") (pintype "power_in"))
    )
    (net (code "33") (name "Net-(U302-A)") (class "Default")
      (node (ref "JP302") (pin "1") (pinfunction "1_1") (pintype "passive"))
      (node (ref "U302") (pin "7") (pinfunction "A_7") (pintype "output"))
    )
    (net (code "34") (name "Net-(U302-B)") (class "Default")
      (node (ref "JP302") (pin "2") (pinfunction "2_2") (pintype "passive"))
      (node (ref "U302") (pin "6") (pinfunction "B_6") (pintype "output"))
    )
    (net (code "35") (name "Net-(U302-MOSI)") (class "Default")
      (node (ref "R315") (pin "2") (pinfunction "2_2") (pintype "passive"))
      (node (ref "U302") (pin "4") (pinfunction "MOSI_4") (pintype "input"))
    )
    (net (code "36") (name "Net-(U400-OUTA1)") (class "Default")
      (node (ref "JP401") (pin "1") (pinfunction "1_1") (pintype "passive"))
      (node (ref "U400") (pin "10") (pinfunction "OUTB1_10") (pintype "output"))
      (node (ref "U400") (pin "3") (pinfunction "OUTA1_3") (pintype "output"))
    )
    (net (code "37") (name "Net-(U400-OUTA2)") (class "Default")
      (node (ref "JP401") (pin "2") (pinfunction "2_2") (pintype "passive"))
      (node (ref "U400") (pin "5") (pinfunction "OUTA2_5") (pintype "output"))
      (node (ref "U400") (pin "8") (pinfunction "OUTB2_8") (pintype "output"))
    )
    (net (code "38") (name "Net-(U400-PH)") (class "Default")
      (node (ref "R405") (pin "1") (pinfunction "1_1") (pintype "passive"))
      (node (ref "U400") (pin "1") (pinfunction "PH_1") (pintype "input"))
    )
    (net (code "39") (name "Net-(U400-PWM)") (class "Default")
      (node (ref "R406") (pin "1") (pinfunction "1_1") (pintype "passive"))
      (node (ref "U400") (pin "2") (pinfunction "PWM_2") (pintype "input"))
    )
    (net (code "40") (name "Net-(U400-REF)") (class "Default")
      (node (ref "C407") (pin "2") (pinfunction "2_2") (pintype "passive"))
      (node (ref "R409") (pin "2") (pinfunction "2_2") (pintype "passive"))
      (node (ref "R410") (pin "1") (pinfunction "1_1") (pintype "passive"))
      (node (ref "U400") (pin "11") (pinfunction "REF_11") (pintype "passive"))
    )
    (net (code "41") (name "Net-(U400-SENSEA)") (class "Default")
      (node (ref "R414") (pin "1") (pinfunction "1_1") (pintype "passive"))
      (node (ref "R415") (pin "1") (pinfunction "1_1") (pintype "passive"))
      (node (ref "R416") (pin "1") (pinfunction "1_1") (pintype "passive"))
      (node (ref "U400") (pin "4") (pinfunction "SENSEA_4") (pintype "output"))
      (node (ref "U400") (pin "9") (pinfunction "SENSEB_9") (pintype "output"))
    )
    (net (code "42") (name "Net-(U400-TOFF)") (class "Default")
      (node (ref "R407") (pin "1") (pinfunction "1_1") (pintype "passive"))
      (node (ref "R408") (pin "1") (pinfunction "1_1") (pintype "passive"))
      (node (ref "U400") (pin "12") (pinfunction "TOFF_12") (pintype "passive"))
    )
    (net (code "43") (name "Net-(U400-VS)") (class "Default")
      (node (ref "C401") (pin "1") (pinfunction "1_1") (pintype "passive"))
      (node (ref "C402") (pin "1") (pinfunction "1_1") (pintype "passive"))
      (node (ref "C403") (pin "1") (pinfunction "1_1") (pintype "passive"))
      (node (ref "R403") (pin "1") (pinfunction "1_1") (pintype "passive"))
      (node (ref "U400") (pin "6") (pinfunction "VS_6") (pintype "power_in"))
    )
    (net (code "44") (name "PA0{slash}CURR_FDB_MAG") (class "Default")
      (node (ref "R419") (pin "1") (pinfunction "1_1") (pintype "passive"))
      (node (ref "U100") (pin "6") (pinfunction "PA0_6") (pintype "bidirectional"))
    )
    (net (code "45") (name "PA1{slash}CURR_FDB_BLDC") (class "Default")
      (node (ref "R314") (pin "1") (pinfunction "1_1") (pintype "passive"))
      (node (ref "U100") (pin "7") (pinfunction "PA1_7") (pintype "bidirectional"))
    )
    (net (code "46") (name "PA2{slash}USART2_TX") (class "Default")
      (node (ref "JP103") (pin "P$2") (pinfunction "TXO_P$2") (pintype "passive"))
      (node (ref "U100") (pin "8") (pinfunction "PA2_8") (pintype "bidirectional"))
    )
    (net (code "47") (name "PA3{slash}USART2_RX") (class "Default")
      (node (ref "JP103") (pin "P$3") (pinfunction "RXI_P$3") (pintype "passive"))
      (node (ref "U100") (pin "9") (pinfunction "PA3_9") (pintype "bidirectional"))
    )
    (net (code "48") (name "PA4{slash}FAULT_BLDC") (class "Default")
      (node (ref "C305") (pin "2") (pinfunction "2_2") (pintype "passive"))
      (node (ref "R302") (pin "1") (pinfunction "1_1") (pintype "passive"))
      (node (ref "U100") (pin "10") (pinfunction "PA4_10") (pintype "bidirectional"))
      (node (ref "U300") (pin "13") (pinfunction "EN/FAULT_13") (pintype "bidirectional"))
    )
    (net (code "49") (name "PA5{slash}SPI1_SCK") (class "Default")
      (node (ref "U100") (pin "11") (pinfunction "PA5_11") (pintype "bidirectional"))
      (node (ref "U302") (pin "2") (pinfunction "SCLK_2") (pintype "input"))
    )
    (net (code "50") (name "PA6{slash}SPI1_NSS") (class "Default")
      (node (ref "U100") (pin "12") (pinfunction "PA6_12") (pintype "bidirectional"))
      (node (ref "U302") (pin "1") (pinfunction "CSN_1") (pintype "input"))
    )
    (net (code "51") (name "PA7{slash}INUL") (class "Default")
      (node (ref "U100") (pin "13") (pinfunction "PA7_13") (pintype "bidirectional"))
      (node (ref "U300") (pin "1") (pinfunction "INUL_1") (pintype "input"))
    )
    (net (code "52") (name "PA8{slash}INUH{slash}PWM_MAG") (class "Default")
      (node (ref "R406") (pin "2") (pinfunction "2_2") (pintype "passive"))
      (node (ref "U100") (pin "18") (pinfunction "PA8_18") (pintype "bidirectional"))
      (node (ref "U300") (pin "2") (pinfunction "INUH_2") (pintype "input"))
    )
    (net (code "53") (name "PA9{slash}INVH{slash}DIR_MAG") (class "Default")
      (node (ref "R405") (pin "2") (pinfunction "2_2") (pintype "passive"))
      (node (ref "U100") (pin "19") (pinfunction "PA9_19") (pintype "bidirectional"))
      (node (ref "U300") (pin "16") (pinfunction "INVH_16") (pintype "input"))
    )
    (net (code "54") (name "PA10{slash}INWH") (class "Default")
      (node (ref "U100") (pin "20") (pinfunction "PA10_20") (pintype "bidirectional"))
      (node (ref "U300") (pin "12") (pinfunction "INWH_12") (pintype "input"))
    )
    (net (code "55") (name "PA15{slash}CAN_SILENT") (class "Default")
      (node (ref "U100") (pin "25") (pinfunction "PA15_25") (pintype "bidirectional"))
      (node (ref "U101") (pin "8") (pinfunction "S_8") (pintype "input"))
    )
    (net (code "56") (name "PB0{slash}INVL") (class "Default")
      (node (ref "U100") (pin "14") (pinfunction "PB0_14") (pintype "bidirectional"))
      (node (ref "U300") (pin "15") (pinfunction "INVL_15") (pintype "input"))
    )
    (net (code "57") (name "PB1{slash}INWL") (class "Default")
      (node (ref "U100") (pin "15") (pinfunction "PB1_15") (pintype "bidirectional"))
      (node (ref "U300") (pin "11") (pinfunction "INWL_11") (pintype "input"))
    )
    (net (code "58") (name "PB3{slash}EN_MAG") (class "Default")
      (node (ref "R402") (pin "2") (pinfunction "2_2") (pintype "passive"))
      (node (ref "U100") (pin "26") (pinfunction "PB3_26") (pintype "bidirectional"))
    )
    (net (code "59") (name "PB4{slash}SPI1_MISO") (class "Default")
      (node (ref "U100") (pin "27") (pinfunction "PB4_27") (pintype "bidirectional"))
      (node (ref "U302") (pin "3") (pinfunction "MISO_3") (pintype "output"))
    )
    (net (code "60") (name "PB5") (class "Default")
      (node (ref "U100") (pin "28") (pinfunction "PB5_28") (pintype "bidirectional"))
    )
    (net (code "61") (name "PB6{slash}EN_BLDC") (class "Default")
      (node (ref "R302") (pin "2") (pinfunction "2_2") (pintype "passive"))
      (node (ref "U100") (pin "29") (pinfunction "PB6_29") (pintype "bidirectional"))
    )
    (net (code "62") (name "PB7{slash}FAULT_MAG") (class "Default")
      (node (ref "C405") (pin "2") (pinfunction "2_2") (pintype "passive"))
      (node (ref "R402") (pin "1") (pinfunction "1_1") (pintype "passive"))
      (node (ref "U100") (pin "30") (pinfunction "PB7_30") (pintype "bidirectional"))
      (node (ref "U400") (pin "13") (pinfunction "EN/FAULT_13") (pintype "bidirectional"))
    )
    (net (code "63") (name "STBY{slash}RESET_BLDC") (class "Default")
      (node (ref "TP2") (pin "TP") (pinfunction "TP_TP") (pintype "input"))
      (node (ref "U300") (pin "14") (pinfunction "STBY/RESET_14") (pintype "input"))
    )
    (net (code "64") (name "STBY{slash}RESET_MAG") (class "Default")
      (node (ref "TP3") (pin "TP") (pinfunction "TP_TP") (pintype "input"))
      (node (ref "U400") (pin "14") (pinfunction "STBY/RESET_14") (pintype "bidirectional"))
    )
    (net (code "65") (name "SWCLK") (class "Default")
      (node (ref "J1") (pin "SWDCLK") (pinfunction "SWDCLK/TCK_SWDCLK") (pintype "passive"))
      (node (ref "U100") (pin "24") (pinfunction "PA14-SWCLK_24") (pintype "bidirectional"))
    )
    (net (code "66") (name "SWDIO") (class "Default")
      (node (ref "J1") (pin "SWDIO") (pinfunction "SWDIO/TMS_SWDIO") (pintype "passive"))
      (node (ref "U100") (pin "23") (pinfunction "PA13-SWDIO_23") (pintype "bidirectional"))
    )
    (net (code "67") (name "V_BATT") (class "Default")
      (node (ref "JP1") (pin "1") (pinfunction "1_1") (pintype "passive"))
      (node (ref "JP103") (pin "P$4") (pinfunction "VCC_P$4") (pintype "passive"))
      (node (ref "R201") (pin "2") (pinfunction "2_2") (pintype "passive"))
      (node (ref "R303") (pin "2") (pinfunction "2_2") (pintype "passive"))
      (node (ref "R403") (pin "2") (pinfunction "2_2") (pintype "passive"))
    )
    (net (code "68") (name "unconnected-(J1-NC{slash}TDI-PadNC)") (class "Default")
      (node (ref "J1") (pin "NC") (pinfunction "NC/TDI_NC") (pintype "passive"))
    )
    (net (code "69") (name "unconnected-(J1-PadGNDDET)") (class "Default")
      (node (ref "J1") (pin "GNDDET") (pinfunction "GNDDET_GNDDET") (pintype "passive"))
    )
    (net (code "70") (name "unconnected-(J1-SWO{slash}TDO-PadSWO)") (class "Default")
      (node (ref "J1") (pin "SWO") (pinfunction "SWO/TDO_SWO") (pintype "passive"))
    )
    (net (code "71") (name "unconnected-(JP103-CTS-PadP$5)") (class "Default")
      (node (ref "JP103") (pin "P$5") (pinfunction "CTS_P$5") (pintype "passive"))
    )
    (net (code "72") (name "unconnected-(JP103-DTR-PadP$1)") (class "Default")
      (node (ref "JP103") (pin "P$1") (pinfunction "DTR_P$1") (pintype "passive"))
    )
    (net (code "73") (name "unconnected-(U302-I{slash}PWM-Pad14)") (class "Default")
      (node (ref "U302") (pin "14") (pinfunction "I/PWM_14") (pintype "output"))
    )
    (net (code "74") (name "unconnected-(U302-U-Pad10)") (class "Default")
      (node (ref "U302") (pin "10") (pinfunction "U_10") (pintype "output"))
    )
    (net (code "75") (name "unconnected-(U302-V-Pad9)") (class "Default")
      (node (ref "U302") (pin "9") (pinfunction "V_9") (pintype "output"))
    )
    (net (code "76") (name "unconnected-(U302-W{slash}PWM-Pad8)") (class "Default")
      (node (ref "U302") (pin "8") (pinfunction "W/PWM_8") (pintype "output"))
    )
  )
)
